# STM32F103T8.net
KiCad netlist of a schematic drawn in Altium Designer
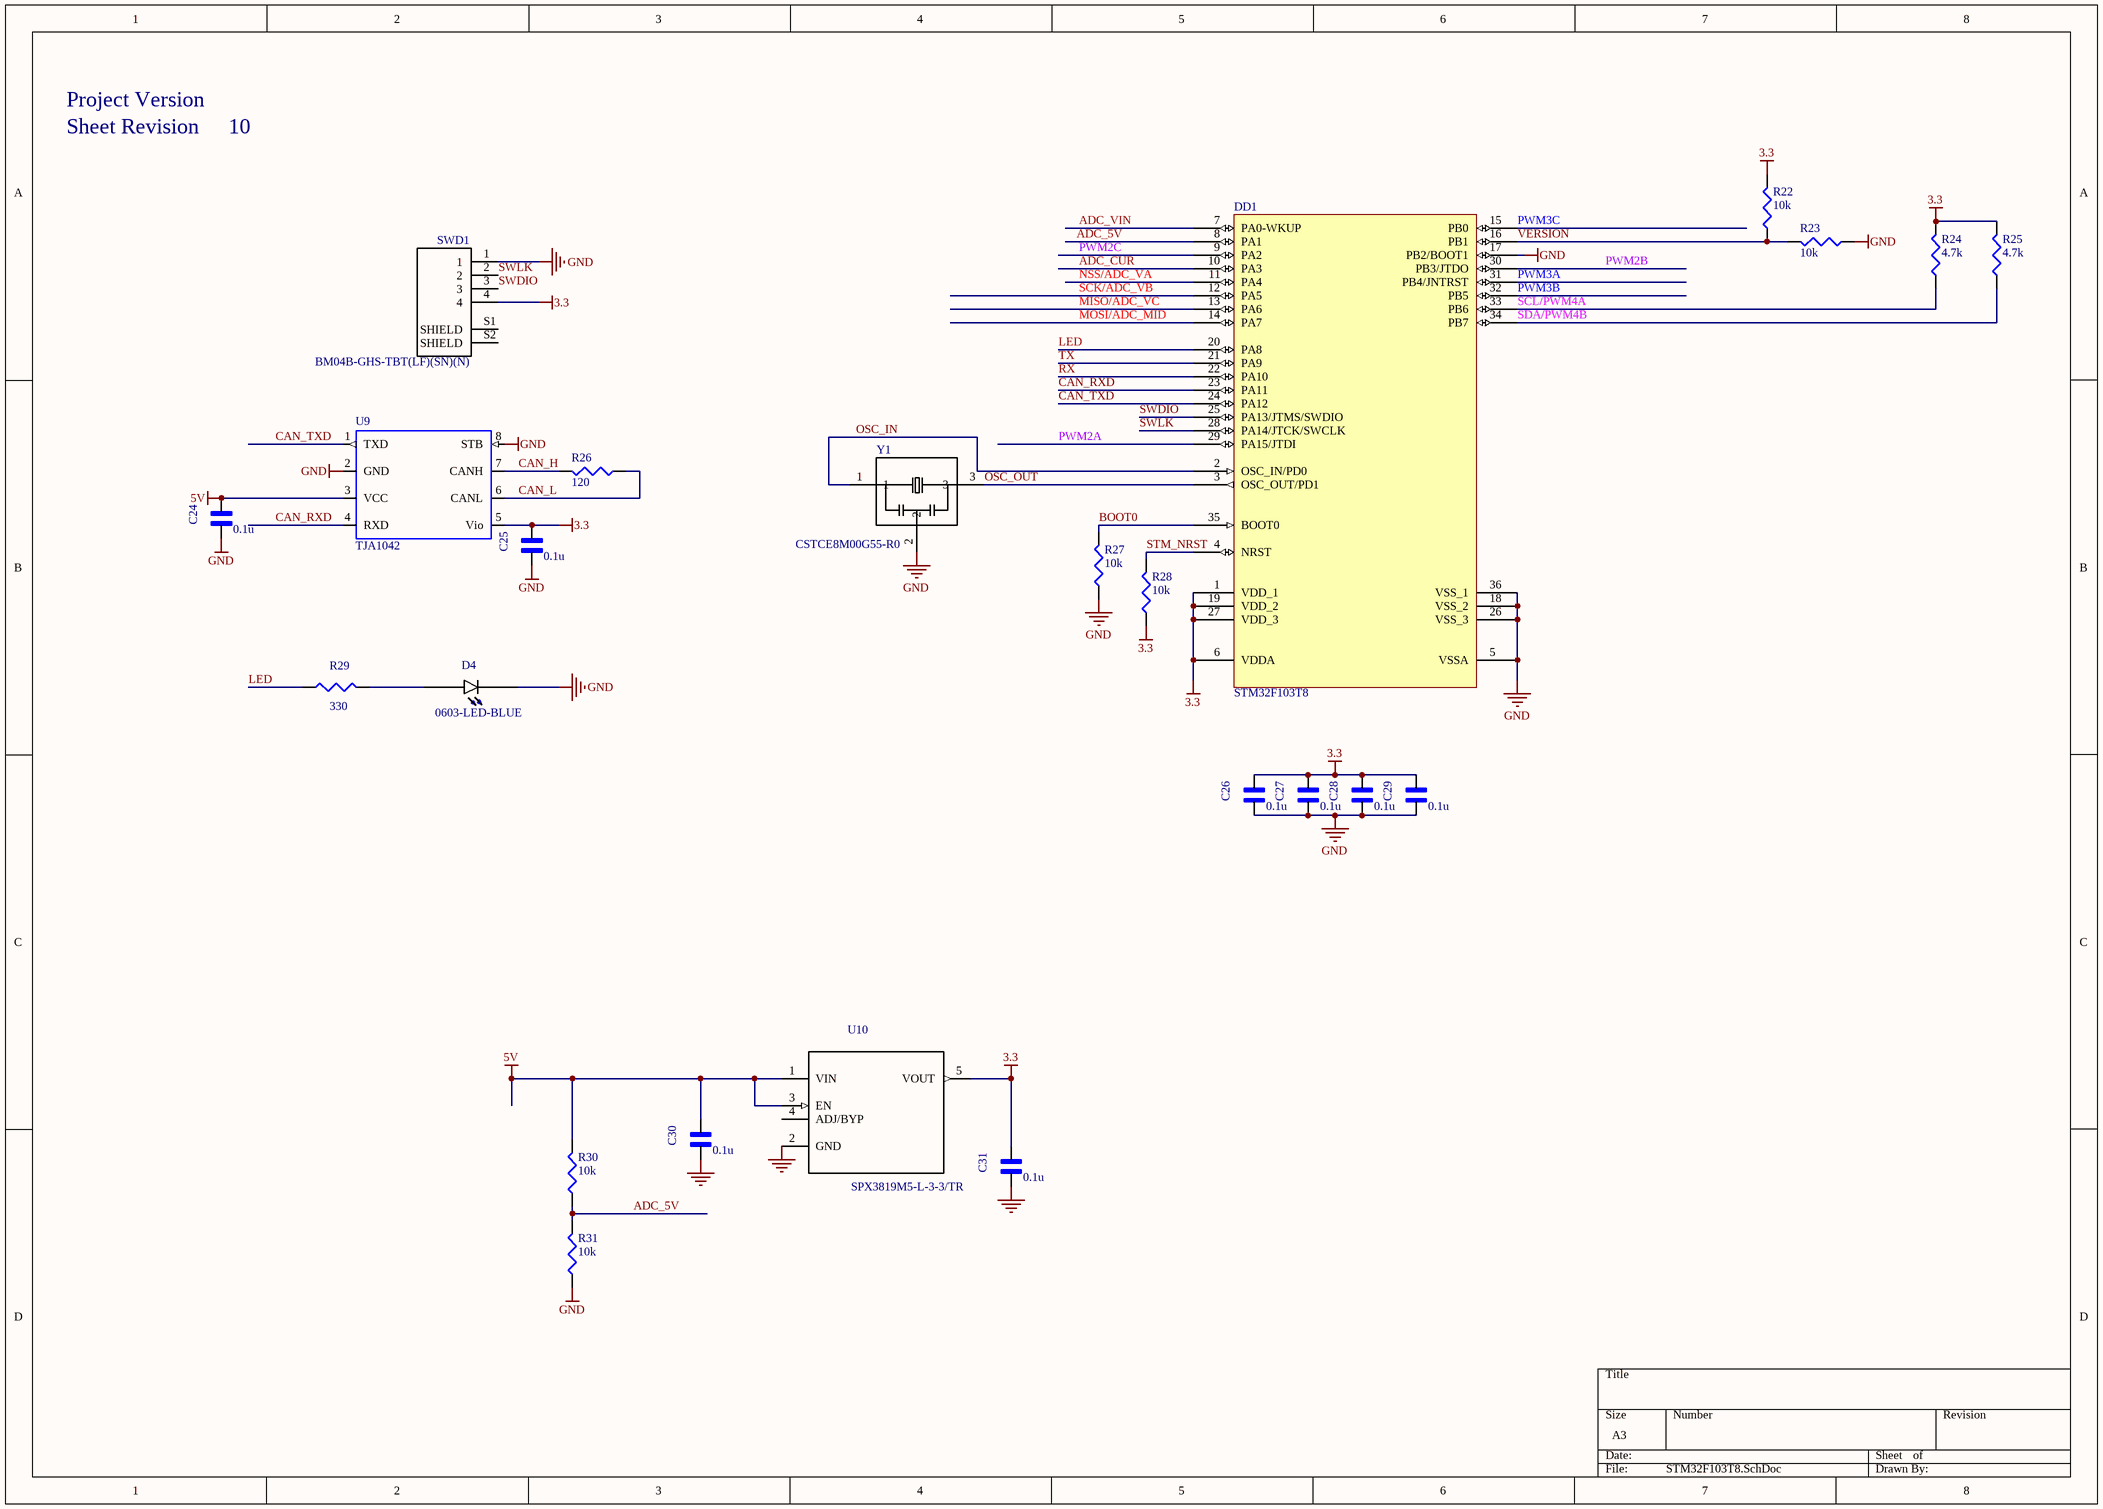
[diagram p0: STM32F103T8.SchDoc]

(export (version "E")
  (design (tool "Eeschema 10.0.6"))
  (components
    (comp (ref "C24")
      (value "0.1u")
      (footprint "*CAPC1608X90")
      (description "Cap Thin Film 0.1uf 50v 0603")
      (fields (field (name "MF") "AVX") (field (name "MP") "GX035C104MAT2-500 or CL10B104JB8NNNC"))
      (libsource (lib "lib") (part "GX035C104MAT2-500"))
    )
    (comp (ref "C25")
      (value "0.1u")
      (footprint "*CAPC1608X90")
      (description "Cap Thin Film 0.1uf 50v 0603")
      (fields (field (name "MF") "AVX") (field (name "MP") "GX035C104MAT2-500 or CL10B104JB8NNNC"))
      (libsource (lib "lib") (part "GX035C104MAT2-500"))
    )
    (comp (ref "C26")
      (value "0.1u")
      (footprint "*CAPC1608X90")
      (description "Cap Thin Film 0.1uf 50v 0603")
      (fields (field (name "MF") "AVX") (field (name "MP") "GX035C104MAT2-500 or CL10B104JB8NNNC"))
      (libsource (lib "lib") (part "GX035C104MAT2-500"))
    )
    (comp (ref "C27")
      (value "0.1u")
      (footprint "*CAPC1608X90")
      (description "Cap Thin Film 0.1uf 50v 0603")
      (fields (field (name "MF") "AVX") (field (name "MP") "GX035C104MAT2-500 or CL10B104JB8NNNC"))
      (libsource (lib "lib") (part "GX035C104MAT2-500"))
    )
    (comp (ref "C28")
      (value "0.1u")
      (footprint "*CAPC1608X90")
      (description "Cap Thin Film 0.1uf 50v 0603")
      (fields (field (name "MF") "AVX") (field (name "MP") "GX035C104MAT2-500 or CL10B104JB8NNNC"))
      (libsource (lib "lib") (part "GX035C104MAT2-500"))
    )
    (comp (ref "C29")
      (value "0.1u")
      (footprint "*CAPC1608X90")
      (description "Cap Thin Film 0.1uf 50v 0603")
      (fields (field (name "MF") "AVX") (field (name "MP") "GX035C104MAT2-500 or CL10B104JB8NNNC"))
      (libsource (lib "lib") (part "GX035C104MAT2-500"))
    )
    (comp (ref "C30")
      (value "0.1u")
      (footprint "*CAPC1608X90")
      (description "Cap Thin Film 0.1uf 50v 0603")
      (fields (field (name "MF") "AVX") (field (name "MP") "GX035C104MAT2-500"))
      (libsource (lib "lib") (part "GX035C104MAT2-500"))
    )
    (comp (ref "C31")
      (value "0.1u")
      (footprint "*CAPC1608X90")
      (description "Cap Thin Film 0.1uf 50v 0603")
      (fields (field (name "MF") "AVX") (field (name "MP") "GX035C104MAT2-500"))
      (libsource (lib "lib") (part "GX035C104MAT2-500"))
    )
    (comp (ref "D4")
      (value "0603-LED-BLUE")
      (footprint "*LEDM1608X80_LTE-C1906R-14(Primary)")
      (description "LED IrLED Chip LED 2-Pin SMD T/R")
      (libsource (lib "lib") (part "LTE-C1906R-14"))
    )
    (comp (ref "DD1")
      (value "STM32F103T8")
      (footprint "*QFN50P600X600X100-37N")
      (description "STM32F103T8U6, Микроконтроллер 32BIT ARM 64K FLASH [VFQFPN-36]")
      (fields (field (name "MF") "STM") (field (name "MP") "STM32F103T8U6"))
      (libsource (lib "lib") (part "STM32F103T8"))
    )
    (comp (ref "R22")
      (value "10k")
      (footprint "J1-0603")
      (description "10 kOhms 1 0.1 W 1 10 W Chip Resistor 0603 1608 Metric Thick Film")
      (fields (field (name "MF") "Yageo or NXP") (field (name "MP") "10K 1% 0603"))
      (libsource (lib "CAN_NODE_MINI") (part "RC0603FR-0710KL"))
    )
    (comp (ref "R23")
      (value "10k")
      (footprint "J1-0603")
      (description "10 kOhms 1 0.1 W 1 10 W Chip Resistor 0603 1608 Metric Thick Film")
      (fields (field (name "MF") "Yageo or NXP") (field (name "MP") "10K 1% 0603"))
      (libsource (lib "CAN_NODE_MINI") (part "RC0603FR-0710KL"))
    )
    (comp (ref "R24")
      (value "4.7k")
      (footprint "J1-0603")
      (description "Resistor")
      (fields (field (name "MP") "4.7K 1% 0603") (field (name "Comment") "Res3"))
      (libsource (lib "Miscellaneous Devices") (part "Res3"))
    )
    (comp (ref "R25")
      (value "4.7k")
      (footprint "J1-0603")
      (description "Resistor")
      (fields (field (name "MP") "4.7K 1% 0603") (field (name "Comment") "Res3"))
      (libsource (lib "Miscellaneous Devices") (part "Res3"))
    )
    (comp (ref "R26")
      (value "120")
      (footprint "J1-0603")
      (description "120 Ohms 1 0.1 W 1 10 W Chip Resistor 0603 1608 Metric Thick Film")
      (fields (field (name "MP") "RC0603FR-07120RL") (field (name "Comment") "Res3"))
      (libsource (lib "Miscellaneous Devices") (part "Res3"))
    )
    (comp (ref "R27")
      (value "10k")
      (footprint "J1-0603")
      (description "10 kOhms 1 0.1 W 1 10 W Chip Resistor 0603 1608 Metric Thick Film")
      (fields (field (name "MF") "Yageo or NXP") (field (name "MP") "10K 1% 0603"))
      (libsource (lib "CAN_NODE_MINI") (part "RC0603FR-0710KL"))
    )
    (comp (ref "R28")
      (value "10k")
      (footprint "J1-0603")
      (description "10 kOhms 1 0.1 W 1 10 W Chip Resistor 0603 1608 Metric Thick Film")
      (fields (field (name "MF") "Yageo or NXP") (field (name "MP") "10K 1% 0603"))
      (libsource (lib "CAN_NODE_MINI") (part "RC0603FR-0710KL"))
    )
    (comp (ref "R29")
      (value "330")
      (footprint "J1-0603")
      (description "Resistor")
      (fields (field (name "MP") "RC0603FR-07330RL") (field (name "Comment") "Res3"))
      (libsource (lib "Miscellaneous Devices") (part "Res3"))
    )
    (comp (ref "R30")
      (value "10k")
      (footprint "J1-0603")
      (description "10 kOhms 1 0.1 W 1 10 W Chip Resistor 0603 1608 Metric Thick Film")
      (fields (field (name "MF") "Yageo or NXP") (field (name "MP") "10K 1% 0603"))
      (libsource (lib "CAN_NODE_MINI") (part "RC0603FR-0710KL"))
    )
    (comp (ref "R31")
      (value "10k")
      (footprint "J1-0603")
      (description "10 kOhms 1 0.1 W 1 10 W Chip Resistor 0603 1608 Metric Thick Film")
      (fields (field (name "MF") "Yageo or NXP") (field (name "MP") "10K 1% 0603"))
      (libsource (lib "CAN_NODE_MINI") (part "RC0603FR-0710KL"))
    )
    (comp (ref "SWD1")
      (value "BM04B-GHS-TBT(LF)(SN)(N)")
      (footprint "JST_BM04B-GHS-holes")
      (description "Conn Shrouded Header HDR 4 POS 1.25mm Solder ST SMD Reel")
      (fields (field (name "MF") "JST Sales") (field (name "MP") "SM04B-GHS-TB(LF)(SN)"))
      (libsource (lib "lib") (part "BM04B-GHS-TBT(LF)(SN)(N)"))
    )
    (comp (ref "U9")
      (value "TJA1042")
      (footprint "SOT782-1")
      (description "1/1 Transceiver Half CANbus 8-SO")
      (fields (field (name "MF") "NXP USA"))
      (libsource (lib "lib") (part "TJA1042"))
    )
    (comp (ref "U10")
      (value "SPX3819M5-L-3-3/TR")
      (footprint "*SOT95P280X145-5N")
      (description "Low Dropout Voltage Regulator, Adjustable 0.5A, В±1%, 2.5 to 16 Vin, 5-Pin SOT-23")
      (fields (field (name "MF") "MaxLinear, Inc."))
      (libsource (lib "DC_DC") (part "SPX3819M5-L"))
    )
    (comp (ref "Y1")
      (value "CSTCE8M00G55-R0")
      (footprint "*OSC_CSTCE8M00G55-R0")
      (description "Ceramic Resonator 8MHz ??0.5% _Tol_ ??0.2% _Stability_ 33pF 40Ohm 3-Pin CSMD T/R")
      (fields (field (name "MF") "Murata"))
      (libsource (lib "DC_DC") (part "CSTCE8M00G55-R0"))
    )
  )
  (nets
    (net (code "1") (name "/ADC_5V") (class "Default")
      (node (ref "DD1") (pin "8") (pinfunction "PA1_8") (pintype "bidirectional"))
      (node (ref "R30") (pin "1") (pinfunction "1_1") (pintype "passive"))
      (node (ref "R31") (pin "2") (pinfunction "2_2") (pintype "passive"))
    )
    (net (code "2") (name "/ADC_CUR") (class "Default")
      (node (ref "DD1") (pin "10") (pinfunction "PA3_10") (pintype "bidirectional"))
    )
    (net (code "3") (name "/ADC_VIN") (class "Default")
      (node (ref "DD1") (pin "7") (pinfunction "PA0-WKUP_7") (pintype "bidirectional"))
    )
    (net (code "4") (name "/BOOT0") (class "Default")
      (node (ref "DD1") (pin "35") (pinfunction "BOOT0_35") (pintype "input"))
      (node (ref "R27") (pin "2") (pinfunction "2_2") (pintype "passive"))
    )
    (net (code "5") (name "/CAN_H") (class "Default")
      (node (ref "R26") (pin "2") (pinfunction "2_2") (pintype "passive"))
      (node (ref "U9") (pin "7") (pinfunction "CANH_7") (pintype "bidirectional"))
    )
    (net (code "6") (name "/CAN_L") (class "Default")
      (node (ref "R26") (pin "1") (pinfunction "1_1") (pintype "passive"))
      (node (ref "U9") (pin "6") (pinfunction "CANL_6") (pintype "bidirectional"))
    )
    (net (code "7") (name "/CAN_RXD") (class "Default")
      (node (ref "DD1") (pin "23") (pinfunction "PA11_23") (pintype "bidirectional"))
      (node (ref "U9") (pin "4") (pinfunction "RXD_4") (pintype "bidirectional"))
    )
    (net (code "8") (name "/CAN_TXD") (class "Default")
      (node (ref "DD1") (pin "24") (pinfunction "PA12_24") (pintype "bidirectional"))
      (node (ref "U9") (pin "1") (pinfunction "TXD_1") (pintype "output"))
    )
    (net (code "9") (name "/LED") (class "Default")
      (node (ref "DD1") (pin "20") (pinfunction "PA8_20") (pintype "bidirectional"))
      (node (ref "R29") (pin "1") (pinfunction "1_1") (pintype "passive"))
    )
    (net (code "10") (name "/MISO{slash}ADC_VC") (class "Default")
      (node (ref "DD1") (pin "13") (pinfunction "PA6_13") (pintype "bidirectional"))
    )
    (net (code "11") (name "/MOSI{slash}ADC_MID") (class "Default")
      (node (ref "DD1") (pin "14") (pinfunction "PA7_14") (pintype "bidirectional"))
    )
    (net (code "12") (name "/NSS{slash}ADC_VA") (class "Default")
      (node (ref "DD1") (pin "11") (pinfunction "PA4_11") (pintype "bidirectional"))
    )
    (net (code "13") (name "/OSC_IN") (class "Default")
      (node (ref "DD1") (pin "2") (pinfunction "OSC_IN/PD0_2") (pintype "input"))
      (node (ref "Y1") (pin "1") (pinfunction "1_1") (pintype "passive"))
    )
    (net (code "14") (name "/OSC_OUT") (class "Default")
      (node (ref "DD1") (pin "3") (pinfunction "OSC_OUT/PD1_3") (pintype "output"))
      (node (ref "Y1") (pin "3") (pinfunction "3_3") (pintype "passive"))
    )
    (net (code "15") (name "/PWM2A") (class "Default")
      (node (ref "DD1") (pin "29") (pinfunction "PA15/JTDI_29") (pintype "bidirectional"))
    )
    (net (code "16") (name "/PWM2B") (class "Default")
      (node (ref "DD1") (pin "30") (pinfunction "PB3/JTDO_30") (pintype "bidirectional"))
    )
    (net (code "17") (name "/PWM2C") (class "Default")
      (node (ref "DD1") (pin "9") (pinfunction "PA2_9") (pintype "bidirectional"))
    )
    (net (code "18") (name "/PWM3A") (class "Default")
      (node (ref "DD1") (pin "31") (pinfunction "PB4/JNTRST_31") (pintype "bidirectional"))
    )
    (net (code "19") (name "/PWM3B") (class "Default")
      (node (ref "DD1") (pin "32") (pinfunction "PB5_32") (pintype "bidirectional"))
    )
    (net (code "20") (name "/PWM3C") (class "Default")
      (node (ref "DD1") (pin "15") (pinfunction "PB0_15") (pintype "bidirectional"))
    )
    (net (code "21") (name "/RX") (class "Default")
      (node (ref "DD1") (pin "22") (pinfunction "PA10_22") (pintype "bidirectional"))
    )
    (net (code "22") (name "/SCK{slash}ADC_VB") (class "Default")
      (node (ref "DD1") (pin "12") (pinfunction "PA5_12") (pintype "bidirectional"))
    )
    (net (code "23") (name "/SCL{slash}PWM4A") (class "Default")
      (node (ref "DD1") (pin "33") (pinfunction "PB6_33") (pintype "bidirectional"))
      (node (ref "R24") (pin "1") (pinfunction "1_1") (pintype "passive"))
    )
    (net (code "24") (name "/SDA{slash}PWM4B") (class "Default")
      (node (ref "DD1") (pin "34") (pinfunction "PB7_34") (pintype "bidirectional"))
      (node (ref "R25") (pin "1") (pinfunction "1_1") (pintype "passive"))
    )
    (net (code "25") (name "/STM_NRST") (class "Default")
      (node (ref "DD1") (pin "4") (pinfunction "NRST_4") (pintype "bidirectional"))
      (node (ref "R28") (pin "2") (pinfunction "2_2") (pintype "passive"))
    )
    (net (code "26") (name "/SWDIO") (class "Default")
      (node (ref "DD1") (pin "25") (pinfunction "PA13/JTMS/SWDIO_25") (pintype "bidirectional"))
      (node (ref "SWD1") (pin "3") (pinfunction "3_3") (pintype "passive"))
    )
    (net (code "27") (name "/SWLK") (class "Default")
      (node (ref "DD1") (pin "28") (pinfunction "PA14/JTCK/SWCLK_28") (pintype "bidirectional"))
      (node (ref "SWD1") (pin "2") (pinfunction "2_2") (pintype "passive"))
    )
    (net (code "28") (name "/TX") (class "Default")
      (node (ref "DD1") (pin "21") (pinfunction "PA9_21") (pintype "bidirectional"))
    )
    (net (code "29") (name "/VERSION") (class "Default")
      (node (ref "DD1") (pin "16") (pinfunction "PB1_16") (pintype "bidirectional"))
      (node (ref "R22") (pin "1") (pinfunction "1_1") (pintype "passive"))
      (node (ref "R23") (pin "2") (pinfunction "2_2") (pintype "passive"))
    )
    (net (code "30") (name "3.3") (class "Default")
      (node (ref "C25") (pin "1") (pinfunction "1_1") (pintype "passive"))
      (node (ref "C26") (pin "1") (pinfunction "1_1") (pintype "passive"))
      (node (ref "C27") (pin "1") (pinfunction "1_1") (pintype "passive"))
      (node (ref "C28") (pin "1") (pinfunction "1_1") (pintype "passive"))
      (node (ref "C29") (pin "1") (pinfunction "1_1") (pintype "passive"))
      (node (ref "C31") (pin "1") (pinfunction "1_1") (pintype "passive"))
      (node (ref "DD1") (pin "1") (pinfunction "VDD_1_1") (pintype "power_in"))
      (node (ref "DD1") (pin "19") (pinfunction "VDD_2_19") (pintype "power_in"))
      (node (ref "DD1") (pin "27") (pinfunction "VDD_3_27") (pintype "power_in"))
      (node (ref "DD1") (pin "6") (pinfunction "VDDA_6") (pintype "power_in"))
      (node (ref "R22") (pin "2") (pinfunction "2_2") (pintype "passive"))
      (node (ref "R24") (pin "2") (pinfunction "2_2") (pintype "passive"))
      (node (ref "R25") (pin "2") (pinfunction "2_2") (pintype "passive"))
      (node (ref "R28") (pin "1") (pinfunction "1_1") (pintype "passive"))
      (node (ref "SWD1") (pin "4") (pinfunction "4_4") (pintype "passive"))
      (node (ref "U10") (pin "5") (pinfunction "VOUT_5") (pintype "output"))
      (node (ref "U9") (pin "5") (pinfunction "Vio_5") (pintype "power_in"))
    )
    (net (code "31") (name "5V") (class "Default")
      (node (ref "C24") (pin "1") (pinfunction "1_1") (pintype "passive"))
      (node (ref "C30") (pin "1") (pinfunction "1_1") (pintype "passive"))
      (node (ref "R30") (pin "2") (pinfunction "2_2") (pintype "passive"))
      (node (ref "U10") (pin "1") (pinfunction "VIN_1") (pintype "power_in"))
      (node (ref "U10") (pin "3") (pinfunction "EN_3") (pintype "input"))
      (node (ref "U9") (pin "3") (pinfunction "VCC_3") (pintype "power_in"))
    )
    (net (code "32") (name "GND") (class "Default")
      (node (ref "C24") (pin "2") (pinfunction "2_2") (pintype "passive"))
      (node (ref "C25") (pin "2") (pinfunction "2_2") (pintype "passive"))
      (node (ref "C26") (pin "2") (pinfunction "2_2") (pintype "passive"))
      (node (ref "C27") (pin "2") (pinfunction "2_2") (pintype "passive"))
      (node (ref "C28") (pin "2") (pinfunction "2_2") (pintype "passive"))
      (node (ref "C29") (pin "2") (pinfunction "2_2") (pintype "passive"))
      (node (ref "C30") (pin "2") (pinfunction "2_2") (pintype "passive"))
      (node (ref "C31") (pin "2") (pinfunction "2_2") (pintype "passive"))
      (node (ref "D4") (pin "C") (pinfunction "C_C") (pintype "passive"))
      (node (ref "DD1") (pin "17") (pinfunction "PB2/BOOT1_17") (pintype "bidirectional"))
      (node (ref "DD1") (pin "18") (pinfunction "VSS_2_18") (pintype "power_in"))
      (node (ref "DD1") (pin "26") (pinfunction "VSS_3_26") (pintype "power_in"))
      (node (ref "DD1") (pin "36") (pinfunction "VSS_1_36") (pintype "power_in"))
      (node (ref "DD1") (pin "5") (pinfunction "VSSA_5") (pintype "power_in"))
      (node (ref "R23") (pin "1") (pinfunction "1_1") (pintype "passive"))
      (node (ref "R27") (pin "1") (pinfunction "1_1") (pintype "passive"))
      (node (ref "R31") (pin "1") (pinfunction "1_1") (pintype "passive"))
      (node (ref "SWD1") (pin "1") (pinfunction "1_1") (pintype "passive"))
      (node (ref "U10") (pin "2") (pinfunction "GND_2") (pintype "passive"))
      (node (ref "U9") (pin "2") (pinfunction "GND_2") (pintype "power_in"))
      (node (ref "U9") (pin "8") (pinfunction "STB_8") (pintype "input"))
      (node (ref "Y1") (pin "2") (pinfunction "2_2") (pintype "power_in"))
    )
    (net (code "33") (name "Net-(D4-PadA)") (class "Default")
      (node (ref "D4") (pin "A") (pinfunction "A_A") (pintype "passive"))
      (node (ref "R29") (pin "2") (pinfunction "2_2") (pintype "passive"))
    )
    (net (code "34") (name "unconnected-(SWD1-SHIELD-PadS1)") (class "Default")
      (node (ref "SWD1") (pin "S1") (pinfunction "SHIELD_S1") (pintype "passive"))
    )
    (net (code "35") (name "unconnected-(SWD1-SHIELD-PadS2)") (class "Default")
      (node (ref "SWD1") (pin "S2") (pinfunction "SHIELD_S2") (pintype "passive"))
    )
    (net (code "36") (name "unconnected-(U10-ADJ{slash}BYP-Pad4)") (class "Default")
      (node (ref "U10") (pin "4") (pinfunction "ADJ/BYP_4") (pintype "passive"))
    )
  )
)
